# Sheet1.net
KiCad netlist of a schematic drawn in Altium Designer
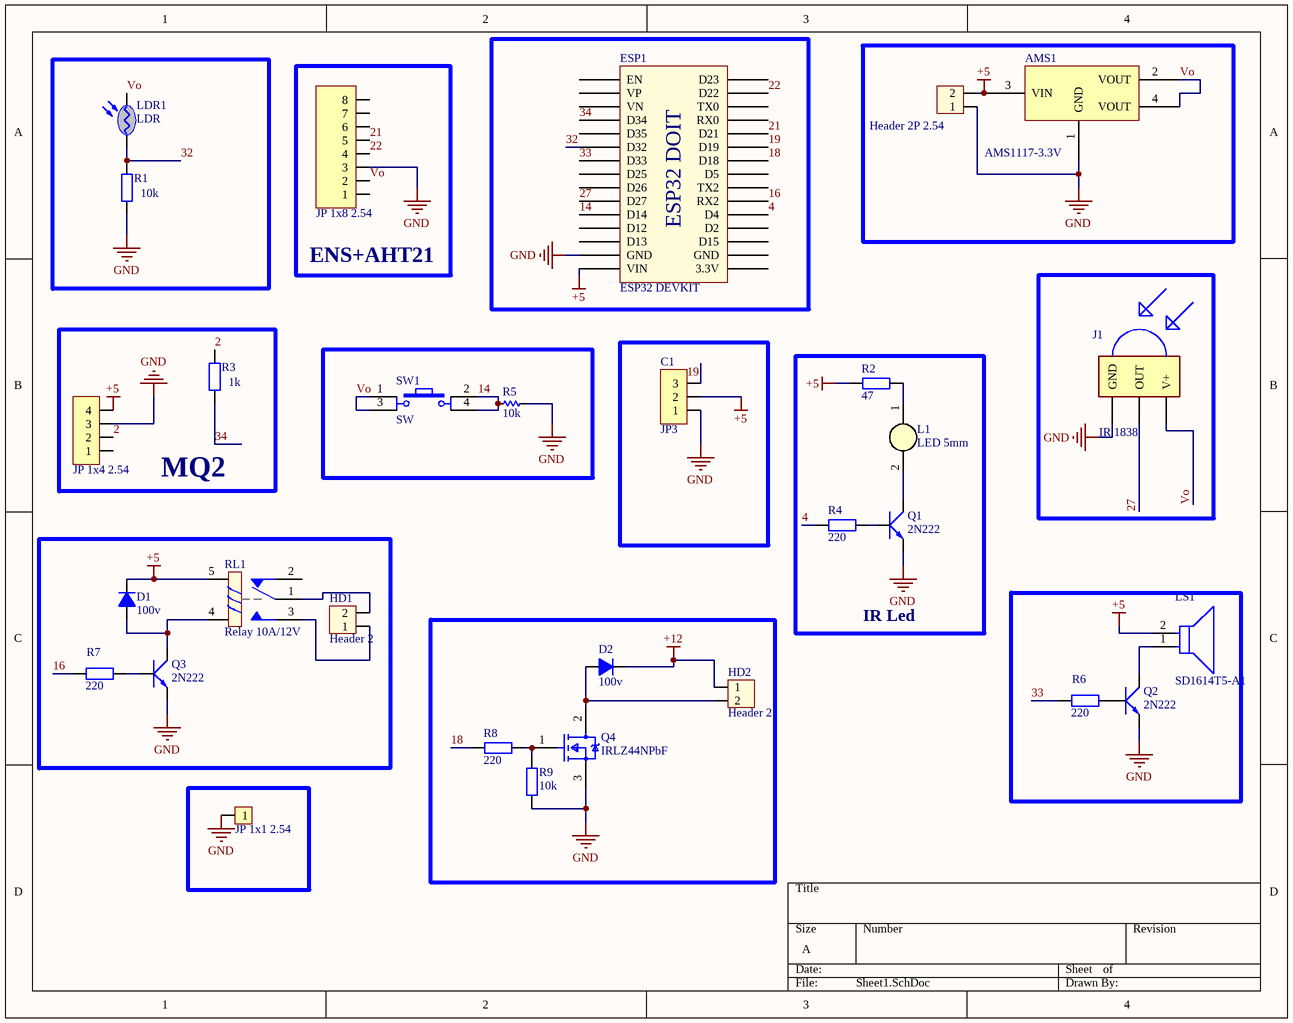
[diagram p0: Sheet1.SchDoc]

(export (version "E")
  (design (tool "Eeschema 10.0.6"))
  (components
    (comp (ref "AMS1")
      (value "AMS1117-3.3V")
      (footprint "SOT223")
      (description "Dán")
      (libsource (lib "Altium_Lib_by_KhueNguyenCreator") (part "AMS1117 SMD"))
    )
    (comp (ref "C1")
      (value "JP3")
      (footprint "JP3-C1T")
      (description "WR-PHD 2.54 mm Angled Socket Header")
      (fields
        (field (name "MANUFACTURER") "Würth Elektronik eiSos GmbH")
        (field (name "PARTNO") "613003143121")
        (field (name "CREATED BY") "Karrer Zheng")
      )
      (libsource (lib "Altium Library") (part "JP3"))
    )
    (comp (ref "D1")
      (value "100v")
      (footprint "DIODE 1A")
      (description "Cắm")
      (libsource (lib "Altium_Lib_by_KhueNguyenCreator") (part "Diode 1N4007"))
    )
    (comp (ref "D2")
      (value "100v")
      (footprint "DIODE 1A")
      (description "Cắm")
      (libsource (lib "Altium_Lib_by_KhueNguyenCreator") (part "Diode 1N4007"))
    )
    (comp (ref "ESP1")
      (value "ESP32 DEVKIT")
      (footprint "ESP32 WROOM 32 KIT")
      (libsource (lib "Altium_Lib_by_KhueNguyenCreator") (part "ESP32 WROOM 32 KIT"))
    )
    (comp (ref "H1")
      (value "Header 2P 2.54")
      (footprint "XH2.54M-2")
      (description "Cắm")
      (libsource (lib "Altium_Lib_by_KhueNguyenCreator") (part "Header 2P 2.54 Duc Thang"))
    )
    (comp (ref "HD1")
      (value "Header 2")
      (footprint "HED2")
      (description "Header 2 (Green)")
      (libsource (lib "syhaunguyen") (part "Hed2"))
    )
    (comp (ref "HD2")
      (value "Header 2")
      (footprint "HED2")
      (description "Header 2 (Green)")
      (libsource (lib "") (part "Hed2_1"))
    )
    (comp (ref "J1")
      (value "IR 1838")
      (footprint "IR 1838")
      (description "IR Receiver and Demodulator")
      (fields (field (name "MP") "TSOP1838"))
      (libsource (lib "Altium_Lib_by_KhueNguyenCreator") (part "IR 1838"))
    )
    (comp (ref "JP1")
      (value "JP 1x8 2.54")
      (footprint "JP 1x8 DT")
      (description "Cắm")
      (libsource (lib "Altium_Lib_by_KhueNguyenCreator") (part "JP 1x8 2.54 Duc Thang"))
    )
    (comp (ref "JP2")
      (value "JP 1x4 2.54")
      (footprint "JP 1x4 CT")
      (description "Cắm")
      (libsource (lib "Altium_Lib_by_KhueNguyenCreator") (part "JP 1x4 2.54 Cai Thang"))
    )
    (comp (ref "JP3")
      (value "JP 1x1 2.54")
      (footprint "JP 1x1 DT")
      (description "Cắm")
      (libsource (lib "Altium_Lib_by_KhueNguyenCreator") (part "JP 1x1 2.54 Duc Cong"))
    )
    (comp (ref "L1")
      (value "LED 5mm")
      (footprint "LED-5MM-WHITE")
      (description "Cắm")
      (libsource (lib "Altium_Lib_by_KhueNguyenCreator") (part "LED 5mm Trang"))
    )
    (comp (ref "LDR1")
      (value "LDR")
      (footprint "CDS")
      (description "Quang Tro")
      (libsource (lib "Altium Library") (part "LDR"))
    )
    (comp (ref "LS1")
      (value "SD1614T5-A1")
      (footprint "FP-SD1614T5-A1-MFG")
      (description "BUZZER MAGNETIC 5V 80DB 2048HZ 1")
      (libsource (lib "Components - 09.03.26 - 20.38") (part "CMP-08413-000005-1"))
    )
    (comp (ref "Q1")
      (value "2N222")
      (footprint "TO92-123")
      (description "NPN 600mW, ECB")
      (libsource (lib "Altium Library") (part "2N222"))
    )
    (comp (ref "Q2")
      (value "2N222")
      (footprint "TO92-123")
      (description "NPN 600mW, ECB")
      (libsource (lib "Altium Library") (part "2N222"))
    )
    (comp (ref "Q3")
      (value "2N222")
      (footprint "TO92-123")
      (description "NPN 600mW, ECB")
      (libsource (lib "Altium Library") (part "2N222"))
    )
    (comp (ref "Q4")
      (value "IRLZ44NPbF")
      (footprint "FP-PG-TO220-3-MFG")
      (description "MOSFET N-CH 55V 47A TO220AB")
      (libsource (lib "Components - 03.03.26 - 22.17") (part "CMP-32901-000488-1"))
    )
    (comp (ref "R1")
      (value "10k")
      (footprint "R1/4W")
      (description "Resistor 1/4W")
      (libsource (lib "syhaunguyen") (part "R1/4W"))
    )
    (comp (ref "R2")
      (value "47")
      (footprint "R1/4W")
      (description "Resistor 1/4W")
      (libsource (lib "syhaunguyen") (part "R1/4W"))
    )
    (comp (ref "R3")
      (value "1k")
      (footprint "R1/4W")
      (description "Resistor 1/4W")
      (libsource (lib "syhaunguyen") (part "R1/4W"))
    )
    (comp (ref "R4")
      (value "220")
      (footprint "R1/4W")
      (description "Resistor 1/4W")
      (libsource (lib "syhaunguyen") (part "R1/4W"))
    )
    (comp (ref "R5")
      (value "10k")
      (footprint "RES-1/2W")
      (description "Res")
      (fields
        (field (name "MANUFACTURER") "Generic Components")
        (field (name "PUBLISHER") "Altium Hobart Technology Centre")
      )
      (libsource (lib "Altium Library") (part "Res"))
    )
    (comp (ref "R6")
      (value "220")
      (footprint "R1/4W")
      (description "Resistor 1/4W")
      (libsource (lib "syhaunguyen") (part "R1/4W"))
    )
    (comp (ref "R7")
      (value "220")
      (footprint "R1/4W")
      (description "Resistor 1/4W")
      (libsource (lib "syhaunguyen") (part "R1/4W"))
    )
    (comp (ref "R8")
      (value "220")
      (footprint "R1/4W")
      (description "Resistor 1/4W")
      (libsource (lib "syhaunguyen") (part "R1/4W"))
    )
    (comp (ref "R9")
      (value "10k")
      (footprint "R1/4W")
      (description "Resistor 1/4W")
      (libsource (lib "syhaunguyen") (part "R1/4W"))
    )
    (comp (ref "RL1")
      (value "Relay 10A/12V")
      (footprint "RELAY 5")
      (description "Relay SPDT,10A - 12VDC 5 Pin")
      (libsource (lib "Altium Library") (part "Relay 5"))
    )
    (comp (ref "SW1")
      (value "SW")
      (footprint "SW4")
      (description "Switch button 4 pin")
      (libsource (lib "syhaunguyen") (part "SW4"))
    )
  )
  (nets
    (net (code "1") (name "+5") (class "Default")
      (node (ref "AMS1") (pin "3") (pinfunction "VIN_3") (pintype "passive"))
      (node (ref "C1") (pin "2") (pinfunction "2_2") (pintype "passive"))
      (node (ref "D1") (pin "2") (pinfunction "K_2") (pintype "passive"))
      (node (ref "ESP1") (pin "15") (pinfunction "VIN_15") (pintype "passive"))
      (node (ref "H1") (pin "2") (pinfunction "2_2") (pintype "passive"))
      (node (ref "JP2") (pin "4") (pinfunction "4_4") (pintype "passive"))
      (node (ref "LS1") (pin "2") (pinfunction "A_2") (pintype "passive"))
      (node (ref "R2") (pin "1") (pinfunction "1_1") (pintype "passive"))
      (node (ref "RL1") (pin "5") (pinfunction "5_5") (pintype "passive"))
    )
    (net (code "2") (name "+12") (class "Default")
      (node (ref "D2") (pin "2") (pinfunction "K_2") (pintype "passive"))
      (node (ref "HD2") (pin "1") (pinfunction "1_1") (pintype "passive"))
    )
    (net (code "3") (name "/2") (class "Default")
      (node (ref "JP2") (pin "2") (pinfunction "2_2") (pintype "passive"))
      (node (ref "R3") (pin "2") (pinfunction "2_2") (pintype "passive"))
    )
    (net (code "4") (name "/4") (class "Default")
      (node (ref "ESP1") (pin "20") (pinfunction "D4_20") (pintype "passive"))
      (node (ref "R4") (pin "1") (pinfunction "1_1") (pintype "passive"))
    )
    (net (code "5") (name "/14") (class "Default")
      (node (ref "ESP1") (pin "11") (pinfunction "D14_11") (pintype "passive"))
      (node (ref "R5") (pin "2") (pinfunction "2_2") (pintype "passive"))
      (node (ref "SW1") (pin "2") (pintype "passive"))
      (node (ref "SW1") (pin "4") (pintype "passive"))
    )
    (net (code "6") (name "/16") (class "Default")
      (node (ref "ESP1") (pin "21") (pinfunction "RX2_21") (pintype "passive"))
      (node (ref "R7") (pin "1") (pinfunction "1_1") (pintype "passive"))
    )
    (net (code "7") (name "/18") (class "Default")
      (node (ref "ESP1") (pin "24") (pinfunction "D18_24") (pintype "passive"))
      (node (ref "R8") (pin "1") (pinfunction "1_1") (pintype "passive"))
    )
    (net (code "8") (name "/19") (class "Default")
      (node (ref "C1") (pin "3") (pinfunction "3_3") (pintype "passive"))
      (node (ref "ESP1") (pin "25") (pinfunction "D19_25") (pintype "passive"))
    )
    (net (code "9") (name "/21") (class "Default")
      (node (ref "ESP1") (pin "26") (pinfunction "D21_26") (pintype "passive"))
      (node (ref "JP1") (pin "5") (pinfunction "5_5") (pintype "passive"))
    )
    (net (code "10") (name "/22") (class "Default")
      (node (ref "ESP1") (pin "29") (pinfunction "D22_29") (pintype "passive"))
      (node (ref "JP1") (pin "4") (pinfunction "4_4") (pintype "passive"))
    )
    (net (code "11") (name "/27") (class "Default")
      (node (ref "ESP1") (pin "10") (pinfunction "D27_10") (pintype "passive"))
      (node (ref "J1") (pin "OUT") (pinfunction "OUT_OUT") (pintype "passive"))
    )
    (net (code "12") (name "/32") (class "Default")
      (node (ref "ESP1") (pin "6") (pinfunction "D32_6") (pintype "passive"))
      (node (ref "LDR1") (pin "1") (pinfunction "A_1") (pintype "passive"))
      (node (ref "R1") (pin "2") (pinfunction "2_2") (pintype "passive"))
    )
    (net (code "13") (name "/33") (class "Default")
      (node (ref "ESP1") (pin "7") (pinfunction "D33_7") (pintype "passive"))
      (node (ref "R6") (pin "1") (pinfunction "1_1") (pintype "passive"))
    )
    (net (code "14") (name "/34") (class "Default")
      (node (ref "ESP1") (pin "4") (pinfunction "D34_4") (pintype "passive"))
      (node (ref "R3") (pin "1") (pinfunction "1_1") (pintype "passive"))
    )
    (net (code "15") (name "/Vo") (class "Default")
      (node (ref "AMS1") (pin "2") (pinfunction "VOUT_2") (pintype "passive"))
      (node (ref "AMS1") (pin "4") (pinfunction "VOUT_4") (pintype "passive"))
      (node (ref "J1") (pin "VCC") (pinfunction "V+_VCC") (pintype "passive"))
      (node (ref "JP1") (pin "2") (pinfunction "2_2") (pintype "passive"))
      (node (ref "LDR1") (pin "2") (pinfunction "K_2") (pintype "passive"))
      (node (ref "SW1") (pin "1") (pintype "passive"))
      (node (ref "SW1") (pin "3") (pintype "passive"))
    )
    (net (code "16") (name "GND") (class "Default")
      (node (ref "AMS1") (pin "1") (pinfunction "GND_1") (pintype "passive"))
      (node (ref "C1") (pin "1") (pinfunction "1_1") (pintype "passive"))
      (node (ref "ESP1") (pin "14") (pinfunction "GND_14") (pintype "passive"))
      (node (ref "H1") (pin "1") (pinfunction "1_1") (pintype "passive"))
      (node (ref "J1") (pin "GND") (pinfunction "GND_GND") (pintype "passive"))
      (node (ref "JP1") (pin "3") (pinfunction "3_3") (pintype "passive"))
      (node (ref "JP2") (pin "3") (pinfunction "3_3") (pintype "passive"))
      (node (ref "JP3") (pin "1") (pinfunction "1_1") (pintype "passive"))
      (node (ref "Q1") (pin "1") (pinfunction "E_1") (pintype "passive"))
      (node (ref "Q2") (pin "1") (pinfunction "E_1") (pintype "passive"))
      (node (ref "Q3") (pin "1") (pinfunction "E_1") (pintype "passive"))
      (node (ref "Q4") (pin "3") (pinfunction "S_3") (pintype "passive"))
      (node (ref "R1") (pin "1") (pinfunction "1_1") (pintype "passive"))
      (node (ref "R5") (pin "1") (pinfunction "1_1") (pintype "passive"))
      (node (ref "R9") (pin "1") (pinfunction "1_1") (pintype "passive"))
    )
    (net (code "17") (name "Net-(D1-A)") (class "Default")
      (node (ref "D1") (pin "1") (pinfunction "A_1") (pintype "passive"))
      (node (ref "Q3") (pin "3") (pinfunction "C_3") (pintype "passive"))
      (node (ref "RL1") (pin "4") (pinfunction "4_4") (pintype "passive"))
    )
    (net (code "18") (name "Net-(D2-A)") (class "Default")
      (node (ref "D2") (pin "1") (pinfunction "A_1") (pintype "passive"))
      (node (ref "HD2") (pin "2") (pinfunction "2_2") (pintype "passive"))
      (node (ref "Q4") (pin "2") (pinfunction "D_2") (pintype "passive"))
    )
    (net (code "19") (name "Net-(HD1-Pad1)") (class "Default")
      (node (ref "HD1") (pin "1") (pinfunction "1_1") (pintype "passive"))
      (node (ref "RL1") (pin "3") (pinfunction "3_3") (pintype "passive"))
    )
    (net (code "20") (name "Net-(HD1-Pad2)") (class "Default")
      (node (ref "HD1") (pin "2") (pinfunction "2_2") (pintype "passive"))
      (node (ref "RL1") (pin "1") (pinfunction "1_1") (pintype "passive"))
    )
    (net (code "21") (name "Net-(L1-A)") (class "Default")
      (node (ref "L1") (pin "1") (pinfunction "A_1") (pintype "passive"))
      (node (ref "R2") (pin "2") (pinfunction "2_2") (pintype "passive"))
    )
    (net (code "22") (name "Net-(L1-K)") (class "Default")
      (node (ref "L1") (pin "2") (pinfunction "K_2") (pintype "passive"))
      (node (ref "Q1") (pin "3") (pinfunction "C_3") (pintype "passive"))
    )
    (net (code "23") (name "Net-(LS1-C)") (class "Default")
      (node (ref "LS1") (pin "1") (pinfunction "C_1") (pintype "passive"))
      (node (ref "Q2") (pin "3") (pinfunction "C_3") (pintype "passive"))
    )
    (net (code "24") (name "Net-(Q1-B)") (class "Default")
      (node (ref "Q1") (pin "2") (pinfunction "B_2") (pintype "passive"))
      (node (ref "R4") (pin "2") (pinfunction "2_2") (pintype "passive"))
    )
    (net (code "25") (name "Net-(Q2-B)") (class "Default")
      (node (ref "Q2") (pin "2") (pinfunction "B_2") (pintype "passive"))
      (node (ref "R6") (pin "2") (pinfunction "2_2") (pintype "passive"))
    )
    (net (code "26") (name "Net-(Q3-B)") (class "Default")
      (node (ref "Q3") (pin "2") (pinfunction "B_2") (pintype "passive"))
      (node (ref "R7") (pin "2") (pinfunction "2_2") (pintype "passive"))
    )
    (net (code "27") (name "Net-(Q4-G)") (class "Default")
      (node (ref "Q4") (pin "1") (pinfunction "G_1") (pintype "passive"))
      (node (ref "R8") (pin "2") (pinfunction "2_2") (pintype "passive"))
      (node (ref "R9") (pin "2") (pinfunction "2_2") (pintype "passive"))
    )
    (net (code "28") (name "unconnected-(ESP1-3.3V-Pad16)") (class "Default")
      (node (ref "ESP1") (pin "16") (pinfunction "3.3V_16") (pintype "passive"))
    )
    (net (code "29") (name "unconnected-(ESP1-D2-Pad19)") (class "Default")
      (node (ref "ESP1") (pin "19") (pinfunction "D2_19") (pintype "passive"))
    )
    (net (code "30") (name "unconnected-(ESP1-D5-Pad23)") (class "Default")
      (node (ref "ESP1") (pin "23") (pinfunction "D5_23") (pintype "passive"))
    )
    (net (code "31") (name "unconnected-(ESP1-D12-Pad12)") (class "Default")
      (node (ref "ESP1") (pin "12") (pinfunction "D12_12") (pintype "passive"))
    )
    (net (code "32") (name "unconnected-(ESP1-D13-Pad13)") (class "Default")
      (node (ref "ESP1") (pin "13") (pinfunction "D13_13") (pintype "passive"))
    )
    (net (code "33") (name "unconnected-(ESP1-D15-Pad18)") (class "Default")
      (node (ref "ESP1") (pin "18") (pinfunction "D15_18") (pintype "passive"))
    )
    (net (code "34") (name "unconnected-(ESP1-D23-Pad30)") (class "Default")
      (node (ref "ESP1") (pin "30") (pinfunction "D23_30") (pintype "passive"))
    )
    (net (code "35") (name "unconnected-(ESP1-D25-Pad8)") (class "Default")
      (node (ref "ESP1") (pin "8") (pinfunction "D25_8") (pintype "passive"))
    )
    (net (code "36") (name "unconnected-(ESP1-D26-Pad9)") (class "Default")
      (node (ref "ESP1") (pin "9") (pinfunction "D26_9") (pintype "passive"))
    )
    (net (code "37") (name "unconnected-(ESP1-D35-Pad5)") (class "Default")
      (node (ref "ESP1") (pin "5") (pinfunction "D35_5") (pintype "passive"))
    )
    (net (code "38") (name "unconnected-(ESP1-EN-Pad1)") (class "Default")
      (node (ref "ESP1") (pin "1") (pinfunction "EN_1") (pintype "passive"))
    )
    (net (code "39") (name "unconnected-(ESP1-GND-Pad17)") (class "Default")
      (node (ref "ESP1") (pin "17") (pinfunction "GND_17") (pintype "passive"))
    )
    (net (code "40") (name "unconnected-(ESP1-RX0-Pad27)") (class "Default")
      (node (ref "ESP1") (pin "27") (pinfunction "RX0_27") (pintype "passive"))
    )
    (net (code "41") (name "unconnected-(ESP1-TX0-Pad28)") (class "Default")
      (node (ref "ESP1") (pin "28") (pinfunction "TX0_28") (pintype "passive"))
    )
    (net (code "42") (name "unconnected-(ESP1-TX2-Pad22)") (class "Default")
      (node (ref "ESP1") (pin "22") (pinfunction "TX2_22") (pintype "passive"))
    )
    (net (code "43") (name "unconnected-(ESP1-VN-Pad3)") (class "Default")
      (node (ref "ESP1") (pin "3") (pinfunction "VN_3") (pintype "passive"))
    )
    (net (code "44") (name "unconnected-(ESP1-VP-Pad2)") (class "Default")
      (node (ref "ESP1") (pin "2") (pinfunction "VP_2") (pintype "passive"))
    )
    (net (code "45") (name "unconnected-(JP1-Pad1)") (class "Default")
      (node (ref "JP1") (pin "1") (pinfunction "1_1") (pintype "passive"))
    )
    (net (code "46") (name "unconnected-(JP1-Pad6)") (class "Default")
      (node (ref "JP1") (pin "6") (pinfunction "6_6") (pintype "passive"))
    )
    (net (code "47") (name "unconnected-(JP1-Pad7)") (class "Default")
      (node (ref "JP1") (pin "7") (pinfunction "7_7") (pintype "passive"))
    )
    (net (code "48") (name "unconnected-(JP1-Pad8)") (class "Default")
      (node (ref "JP1") (pin "8") (pinfunction "8_8") (pintype "passive"))
    )
    (net (code "49") (name "unconnected-(JP2-Pad1)") (class "Default")
      (node (ref "JP2") (pin "1") (pinfunction "1_1") (pintype "passive"))
    )
    (net (code "50") (name "unconnected-(RL1-Pad2)") (class "Default")
      (node (ref "RL1") (pin "2") (pinfunction "2_2") (pintype "passive"))
    )
  )
)
